# EasyPlanter_V1.net
KiCad netlist of a schematic drawn in EAGLE
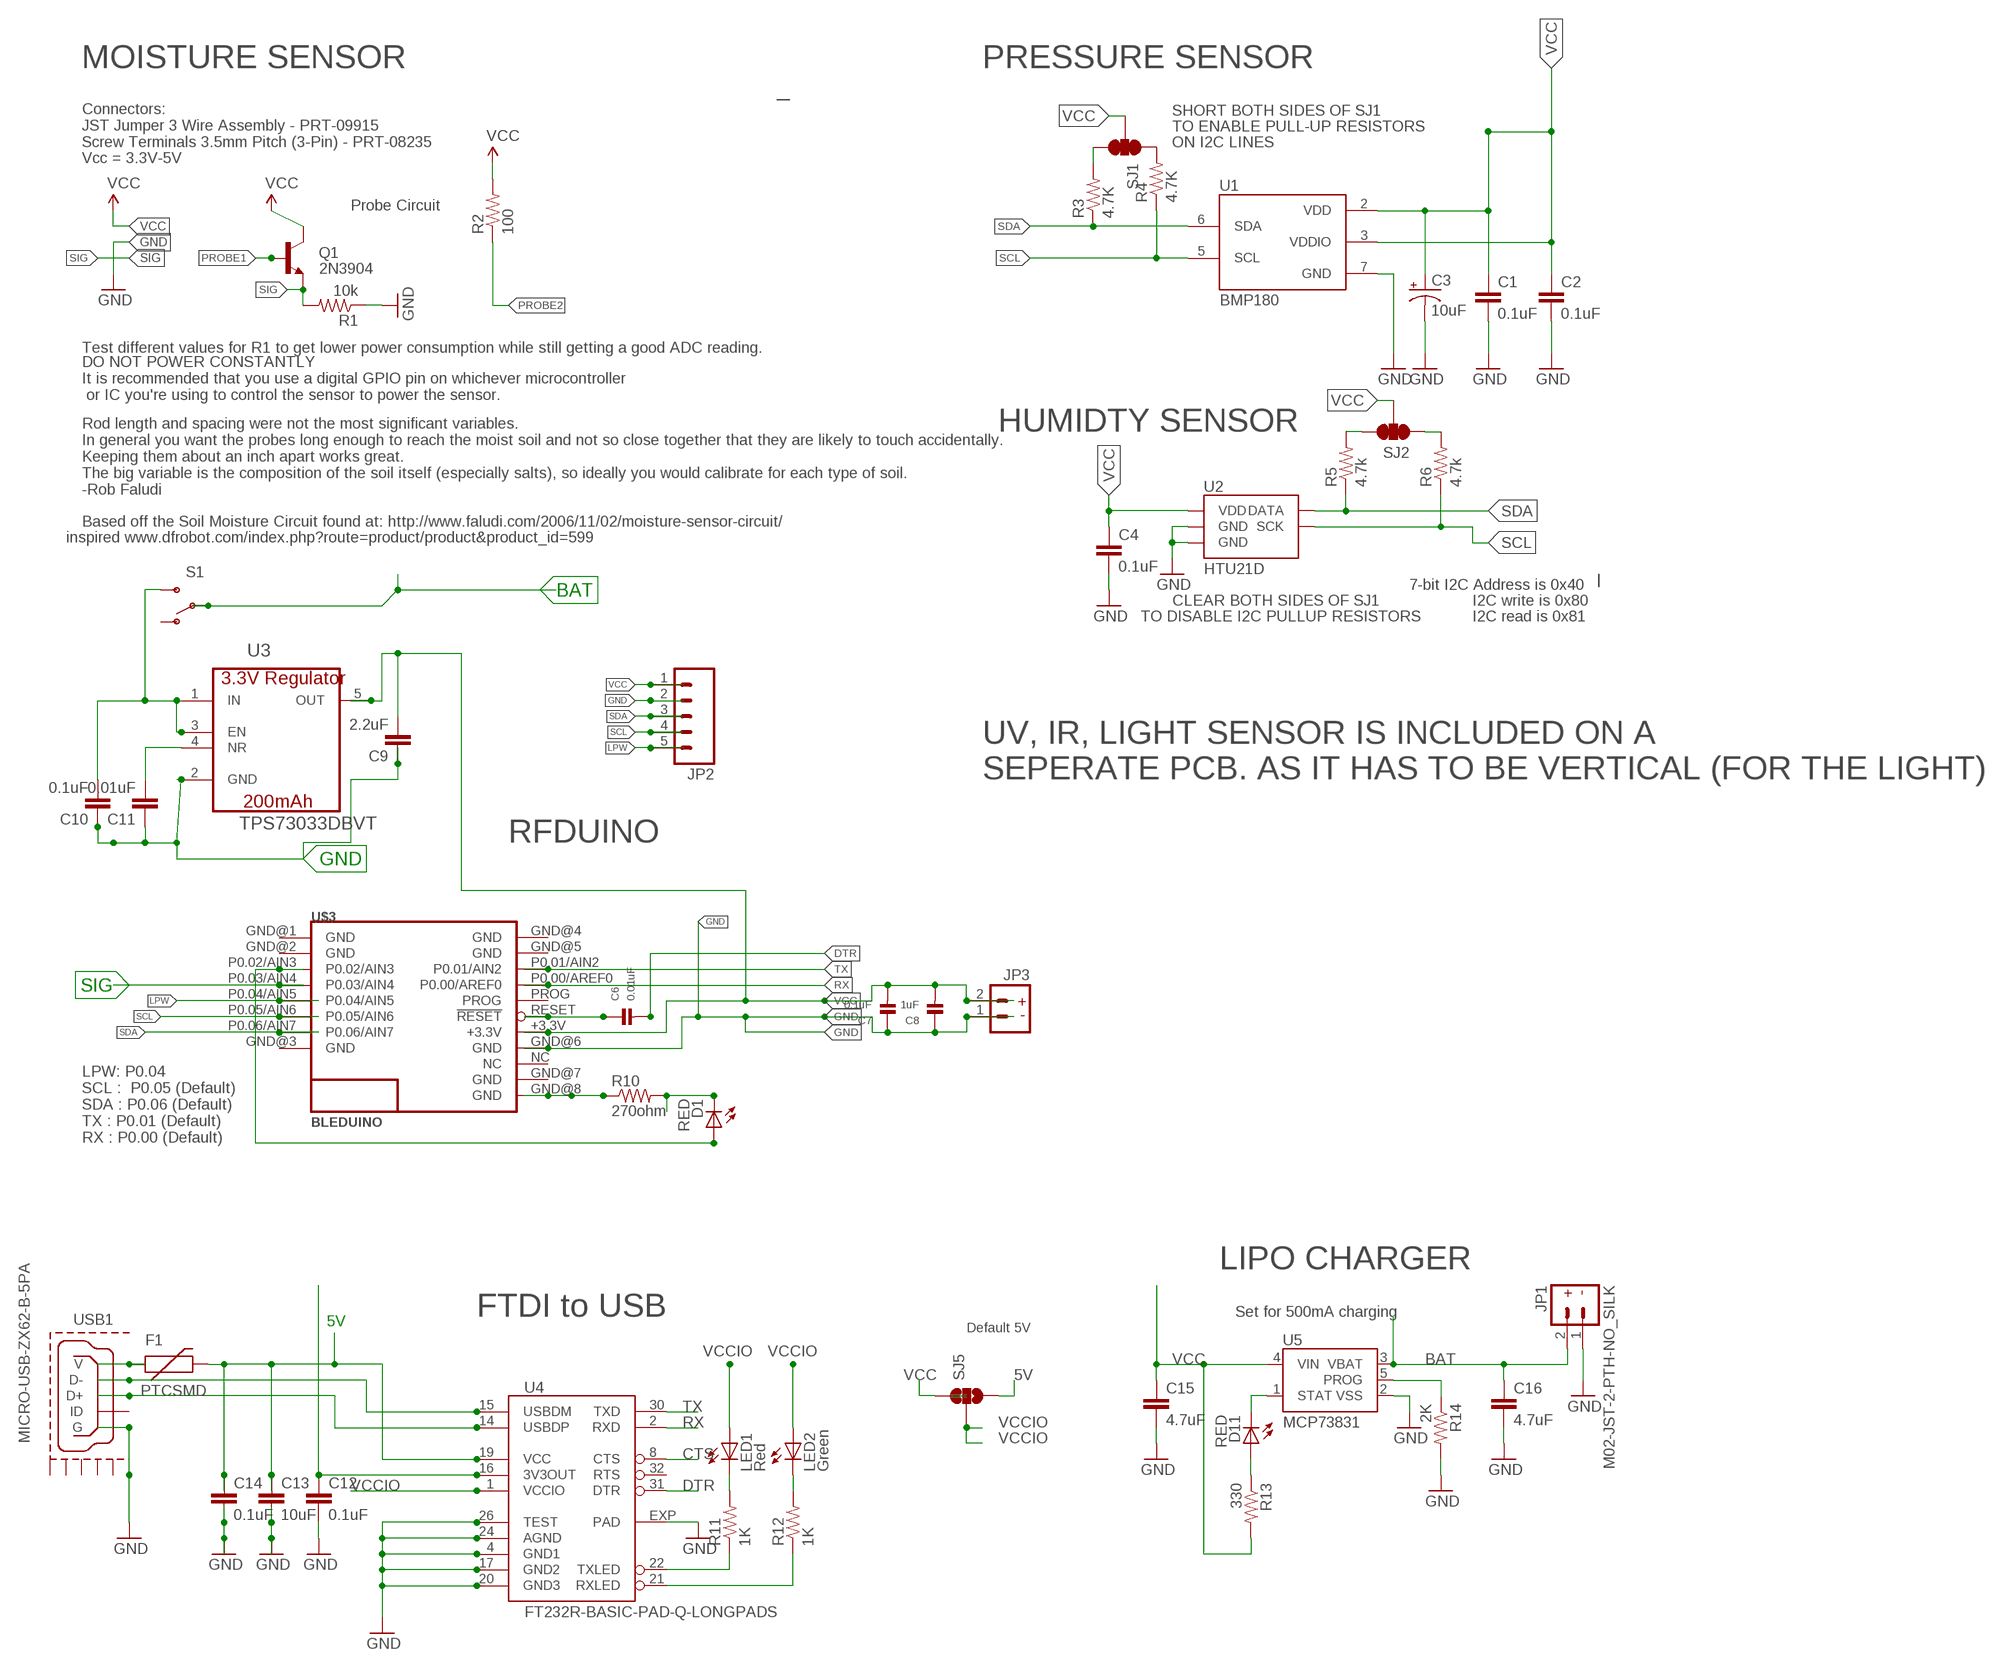
[diagram p0: schematic, sheet 1]

(export (version "E")
  (design (tool "Eeschema 10.0.6"))
  (components
    (comp (ref "C1")
      (value "0.1uF")
      (footprint "eagle-import:0603-CAP")
      (libsource (lib "eagle-import") (part "SparkFun-Capacitors_CAP0603-CAP"))
    )
    (comp (ref "C2")
      (value "0.1uF")
      (footprint "eagle-import:0603-CAP")
      (libsource (lib "eagle-import") (part "SparkFun-Capacitors_CAP0603-CAP"))
    )
    (comp (ref "C3")
      (value "10uF")
      (footprint "eagle-import:EIA3216")
      (libsource (lib "eagle-import") (part "10UF-16V-10%(TANT)"))
    )
    (comp (ref "C4")
      (value "0.1uF")
      (footprint "eagle-import:0603-CAP")
      (libsource (lib "eagle-import") (part "CAP0603-CAP"))
    )
    (comp (ref "C6")
      (value "0.01uF")
      (footprint "eagle-import:0402")
      (libsource (lib "eagle-import") (part "CAP_CERAMIC0402"))
    )
    (comp (ref "C7")
      (value "0.1uF")
      (footprint "eagle-import:0402")
      (libsource (lib "eagle-import") (part "CAP_CERAMIC0402"))
    )
    (comp (ref "C8")
      (value "1uF")
      (footprint "eagle-import:0402")
      (libsource (lib "eagle-import") (part "CAP_CERAMIC0402"))
    )
    (comp (ref "C9")
      (value "2.2uF")
      (footprint "eagle-import:0402-CAP")
      (libsource (lib "eagle-import") (part "CAP0402-CAP"))
    )
    (comp (ref "C10")
      (value "0.1uF")
      (footprint "eagle-import:0402-CAP")
      (libsource (lib "eagle-import") (part "CAP0402-CAP"))
    )
    (comp (ref "C11")
      (value "0.01uF")
      (footprint "eagle-import:0402-CAP")
      (libsource (lib "eagle-import") (part "CAP0402-CAP"))
    )
    (comp (ref "C12")
      (value "0.1uF")
      (footprint "eagle-import:0402-CAP")
      (libsource (lib "eagle-import") (part "CAP-0402"))
    )
    (comp (ref "C13")
      (value "10uF")
      (footprint "eagle-import:0402-CAP")
      (libsource (lib "eagle-import") (part "CAP-0402"))
    )
    (comp (ref "C14")
      (value "0.1uF")
      (footprint "eagle-import:0402-CAP")
      (libsource (lib "eagle-import") (part "CAP-0402"))
    )
    (comp (ref "C15")
      (value "4.7uF")
      (footprint "eagle-import:0402-CAP")
      (libsource (lib "eagle-import") (part "CAP0402-CAP"))
    )
    (comp (ref "C16")
      (value "4.7uF")
      (footprint "eagle-import:0402-CAP")
      (libsource (lib "eagle-import") (part "CAP0402-CAP"))
    )
    (comp (ref "D1")
      (value "RED")
      (footprint "eagle-import:LED-0603")
      (libsource (lib "eagle-import") (part "LED-RED0603"))
    )
    (comp (ref "D11")
      (value "RED")
      (footprint "eagle-import:LED-0603")
      (libsource (lib "eagle-import") (part "LED0603"))
    )
    (comp (ref "F1")
      (value "PTCSMD")
      (footprint "eagle-import:PTC-1206")
      (libsource (lib "eagle-import") (part "PTCSMD"))
    )
    (comp (ref "JP1")
      (value "M02-JST-2-PTH-NO_SILK")
      (footprint "eagle-import:JST-2-PTH-NS")
      (libsource (lib "eagle-import") (part "M02-JST-2-PTH-NO_SILK"))
    )
    (comp (ref "JP2")
      (value "M05PTH")
      (footprint "eagle-import:1X05")
      (libsource (lib "eagle-import") (part "M05PTH"))
    )
    (comp (ref "JP3")
      (value "M02-JST-2-PTH-NO_SILK")
      (footprint "eagle-import:JST-2-PTH-NS")
      (libsource (lib "eagle-import") (part "M02-JST-2-PTH-NO_SILK"))
    )
    (comp (ref "LED1")
      (value "Red")
      (footprint "eagle-import:LED-0603")
      (libsource (lib "eagle-import") (part "akafugu_LED0603"))
    )
    (comp (ref "LED2")
      (value "Green")
      (footprint "eagle-import:LED-0603")
      (libsource (lib "eagle-import") (part "akafugu_LED0603"))
    )
    (comp (ref "Q1")
      (value "2N3904")
      (footprint "eagle-import:SOT23-3")
      (libsource (lib "eagle-import") (part "TRANSISTOR_NPNMMBT2222A"))
    )
    (comp (ref "R1")
      (value "10k")
      (footprint "eagle-import:0603-RES")
      (libsource (lib "eagle-import") (part "100OHM-1/4W-5%(0603)"))
    )
    (comp (ref "R2")
      (value "100")
      (footprint "eagle-import:0603-RES")
      (libsource (lib "eagle-import") (part "100OHM-1/4W-5%(0603)"))
    )
    (comp (ref "R3")
      (value "4.7K")
      (footprint "eagle-import:0603-RES")
      (libsource (lib "eagle-import") (part "SparkFun-Passives_RESISTOR0603-RES"))
    )
    (comp (ref "R4")
      (value "4.7K")
      (footprint "eagle-import:0603-RES")
      (libsource (lib "eagle-import") (part "SparkFun-Passives_RESISTOR0603-RES"))
    )
    (comp (ref "R5")
      (value "4.7k")
      (footprint "eagle-import:0603-RES")
      (libsource (lib "eagle-import") (part "RESISTOR0603-RES"))
    )
    (comp (ref "R6")
      (value "4.7k")
      (footprint "eagle-import:0603-RES")
      (libsource (lib "eagle-import") (part "RESISTOR0603-RES"))
    )
    (comp (ref "R10")
      (value "270ohm")
      (footprint "eagle-import:0402-RES")
      (libsource (lib "eagle-import") (part "SparkFun-Passives_RESISTOR0402-RES"))
    )
    (comp (ref "R11")
      (value "1K")
      (footprint "eagle-import:R0402")
      (libsource (lib "eagle-import") (part "RESISTOR-0402"))
    )
    (comp (ref "R12")
      (value "1K")
      (footprint "eagle-import:R0402")
      (libsource (lib "eagle-import") (part "RESISTOR-0402"))
    )
    (comp (ref "R13")
      (value "330")
      (footprint "eagle-import:0402-RES")
      (libsource (lib "eagle-import") (part "RESISTOR0402-RES"))
    )
    (comp (ref "R14")
      (value "2K")
      (footprint "eagle-import:0402-RES")
      (libsource (lib "eagle-import") (part "RESISTOR0402-RES"))
    )
    (comp (ref "S1")
      (value "SWITCH-SPDT-SMD-A")
      (footprint "eagle-import:SWITCH-SPST-SMD-A")
      (libsource (lib "eagle-import") (part "SWITCH-SPDT-SMD-A"))
    )
    (comp (ref "SJ1")
      (value "SOLDERJUMPER_2WAYPASTE1&2&3")
      (footprint "eagle-import:SJ_3_PASTE1&2&3")
      (libsource (lib "eagle-import") (part "SOLDERJUMPER_2WAYPASTE1&2&3"))
    )
    (comp (ref "SJ2")
      (value "SOLDERJUMPER_2WAYPASTE1&2&3")
      (footprint "eagle-import:SJ_3_PASTE1&2&3")
      (libsource (lib "eagle-import") (part "SOLDERJUMPER_2WAYPASTE1&2&3"))
    )
    (comp (ref "SJ5")
      (value "SOLDERJUMPER_2WAY-LEFT-BRIDGED")
      (footprint "eagle-import:SJ-3-LEFT")
      (libsource (lib "eagle-import") (part "SOLDERJUMPER_2WAY-LEFT-BRIDGED"))
    )
    (comp (ref "U$3")
      (value "BLEDUINO")
      (footprint "eagle-import:BLEDUINO")
      (libsource (lib "eagle-import") (part "BLEDUINO"))
    )
    (comp (ref "U1")
      (value "BMP180")
      (footprint "eagle-import:BMP180")
      (libsource (lib "eagle-import") (part "BMP180"))
    )
    (comp (ref "U2")
      (value "HTU21D")
      (footprint "eagle-import:HTU21D")
      (libsource (lib "eagle-import") (part "HTU21DSMD"))
    )
    (comp (ref "U3")
      (value "TPS73033DBVT")
      (footprint "eagle-import:SOT95P290X145-5N")
      (libsource (lib "eagle-import") (part "TPS73033DBVT"))
    )
    (comp (ref "U4")
      (value "FT232R-BASIC-PAD-Q-LONGPADS")
      (footprint "eagle-import:QFN32-LONG")
      (libsource (lib "eagle-import") (part "FT232R-BASIC-PAD-Q-LONGPADS"))
    )
    (comp (ref "U5")
      (value "MCP73831")
      (footprint "eagle-import:SOT23-5")
      (libsource (lib "eagle-import") (part "MCP73831"))
    )
    (comp (ref "USB1")
      (value "MICRO-USB-ZX62-B-5PA")
      (footprint "eagle-import:ZX62-B-5PA")
      (libsource (lib "eagle-import") (part "MICRO-USB-ZX62-B-5PA"))
    )
  )
  (nets
    (net (code "1") (name "/5V") (class "Default")
      (node (ref "C13") (pin "1") (pinfunction "1_1") (pintype "passive"))
      (node (ref "C14") (pin "1") (pinfunction "1_1") (pintype "passive"))
      (node (ref "F1") (pin "2") (pinfunction "2_2") (pintype "bidirectional"))
      (node (ref "SJ5") (pin "3") (pinfunction "3_3") (pintype "passive"))
      (node (ref "U4") (pin "19") (pinfunction "VCC_19") (pintype "power_in"))
    )
    (net (code "2") (name "/CTS") (class "Default")
      (node (ref "U4") (pin "8") (pinfunction "CTS_8") (pintype "bidirectional"))
    )
    (net (code "3") (name "/GND1") (class "Default")
      (node (ref "USB1") (pin "GND@1") (pinfunction "GND1_GND@1") (pintype "power_in"))
    )
    (net (code "4") (name "/GND2") (class "Default")
      (node (ref "USB1") (pin "GND@2") (pinfunction "GND2_GND@2") (pintype "power_in"))
    )
    (net (code "5") (name "/GND3") (class "Default")
      (node (ref "USB1") (pin "GND@3") (pinfunction "GND3_GND@3") (pintype "power_in"))
    )
    (net (code "6") (name "/GND4") (class "Default")
      (node (ref "USB1") (pin "GND@4") (pinfunction "GND4_GND@4") (pintype "power_in"))
    )
    (net (code "7") (name "/GND5") (class "Default")
      (node (ref "USB1") (pin "GND@5") (pinfunction "GND5_GND@5") (pintype "power_in"))
    )
    (net (code "8") (name "/VCCIO") (class "Default")
      (node (ref "LED1") (pin "A") (pinfunction "A_A") (pintype "passive"))
      (node (ref "LED2") (pin "A") (pinfunction "A_A") (pintype "passive"))
      (node (ref "SJ5") (pin "2") (pinfunction "2_2") (pintype "passive"))
      (node (ref "U4") (pin "1") (pinfunction "VCCIO_1") (pintype "power_in"))
    )
    (net (code "9") (name "BAT") (class "Default")
      (node (ref "C16") (pin "1") (pinfunction "1_1") (pintype "passive"))
      (node (ref "JP1") (pin "2") (pinfunction "2_2") (pintype "passive"))
      (node (ref "S1") (pin "2") (pinfunction "P_2") (pintype "passive"))
      (node (ref "U5") (pin "3") (pinfunction "VBAT_3") (pintype "power_in"))
    )
    (net (code "10") (name "DTR") (class "Default")
      (node (ref "C6") (pin "2") (pinfunction "P$2_2") (pintype "passive"))
      (node (ref "U4") (pin "31") (pinfunction "DTR_31") (pintype "bidirectional"))
    )
    (net (code "11") (name "GND") (class "Default")
      (node (ref "C1") (pin "2") (pinfunction "2_2") (pintype "passive"))
      (node (ref "C10") (pin "1") (pinfunction "1_1") (pintype "passive"))
      (node (ref "C11") (pin "1") (pinfunction "1_1") (pintype "passive"))
      (node (ref "C12") (pin "2") (pinfunction "2_2") (pintype "passive"))
      (node (ref "C13") (pin "2") (pinfunction "2_2") (pintype "passive"))
      (node (ref "C14") (pin "2") (pinfunction "2_2") (pintype "passive"))
      (node (ref "C15") (pin "2") (pinfunction "2_2") (pintype "passive"))
      (node (ref "C16") (pin "2") (pinfunction "2_2") (pintype "passive"))
      (node (ref "C2") (pin "2") (pinfunction "2_2") (pintype "passive"))
      (node (ref "C3") (pin "C") (pinfunction "-_C") (pintype "passive"))
      (node (ref "C4") (pin "2") (pinfunction "2_2") (pintype "passive"))
      (node (ref "C7") (pin "1") (pinfunction "P$1_1") (pintype "passive"))
      (node (ref "C8") (pin "1") (pinfunction "P$1_1") (pintype "passive"))
      (node (ref "C9") (pin "1") (pinfunction "1_1") (pintype "passive"))
      (node (ref "JP1") (pin "1") (pinfunction "1_1") (pintype "passive"))
      (node (ref "JP2") (pin "2") (pinfunction "2_2") (pintype "passive"))
      (node (ref "JP3") (pin "1") (pinfunction "1_1") (pintype "passive"))
      (node (ref "R1") (pin "1") (pinfunction "1_1") (pintype "passive"))
      (node (ref "R14") (pin "2") (pinfunction "2_2") (pintype "passive"))
      (node (ref "U$3") (pin "GND@6") (pinfunction "GND_GND@6") (pintype "bidirectional"))
      (node (ref "U1") (pin "7") (pinfunction "GND_7") (pintype "power_in"))
      (node (ref "U2") (pin "7") (pinfunction "GND_7") (pintype "power_in"))
      (node (ref "U2") (pin "GND") (pinfunction "GND_GND") (pintype "power_in"))
      (node (ref "U3") (pin "2") (pinfunction "GND_2") (pintype "passive"))
      (node (ref "U4") (pin "17") (pinfunction "GND2_17") (pintype "power_in"))
      (node (ref "U4") (pin "20") (pinfunction "GND3_20") (pintype "power_in"))
      (node (ref "U4") (pin "24") (pinfunction "AGND_24") (pintype "power_in"))
      (node (ref "U4") (pin "26") (pinfunction "TEST_26") (pintype "input"))
      (node (ref "U4") (pin "4") (pinfunction "GND1_4") (pintype "power_in"))
      (node (ref "U4") (pin "EXP") (pinfunction "PAD_EXP") (pintype "bidirectional"))
      (node (ref "U5") (pin "2") (pinfunction "VSS_2") (pintype "power_in"))
      (node (ref "USB1") (pin "5") (pinfunction "G_5") (pintype "input"))
      (node (ref "USB1") (pin "GND@6") (pinfunction "GND6_GND@6") (pintype "power_in"))
    )
    (net (code "12") (name "LPW") (class "Default")
      (node (ref "JP2") (pin "5") (pinfunction "5_5") (pintype "passive"))
      (node (ref "U$3") (pin "P0.04/AIN5") (pinfunction "P0.04/AIN5_P0.04/AIN5") (pintype "bidirectional"))
    )
    (net (code "13") (name "Net-(C6-P$1)") (class "Default")
      (node (ref "C6") (pin "1") (pinfunction "P$1_1") (pintype "passive"))
      (node (ref "U$3") (pin "RESET") (pinfunction "~{RESET}_RESET") (pintype "bidirectional"))
    )
    (net (code "14") (name "Net-(D1-PadA)") (class "Default")
      (node (ref "D1") (pin "A") (pinfunction "A_A") (pintype "passive"))
      (node (ref "U$3") (pin "P0.02/AIN3") (pinfunction "P0.02/AIN3_P0.02/AIN3") (pintype "bidirectional"))
    )
    (net (code "15") (name "Net-(D1-PadC)") (class "Default")
      (node (ref "D1") (pin "C") (pinfunction "C_C") (pintype "passive"))
      (node (ref "R10") (pin "2") (pinfunction "2_2") (pintype "passive"))
    )
    (net (code "16") (name "Net-(D11-PadA)") (class "Default")
      (node (ref "D11") (pin "A") (pinfunction "A_A") (pintype "passive"))
      (node (ref "R13") (pin "1") (pinfunction "1_1") (pintype "passive"))
    )
    (net (code "17") (name "Net-(LED1-PadC)") (class "Default")
      (node (ref "LED1") (pin "C") (pinfunction "C_C") (pintype "passive"))
      (node (ref "R11") (pin "2") (pinfunction "2_2") (pintype "passive"))
    )
    (net (code "18") (name "Net-(LED2-PadC)") (class "Default")
      (node (ref "LED2") (pin "C") (pinfunction "C_C") (pintype "passive"))
      (node (ref "R12") (pin "2") (pinfunction "2_2") (pintype "passive"))
    )
    (net (code "19") (name "Net-(R3-Pad2)") (class "Default")
      (node (ref "R3") (pin "2") (pinfunction "2_2") (pintype "passive"))
      (node (ref "SJ1") (pin "3") (pinfunction "3_3") (pintype "passive"))
    )
    (net (code "20") (name "Net-(R4-Pad2)") (class "Default")
      (node (ref "R4") (pin "2") (pinfunction "2_2") (pintype "passive"))
      (node (ref "SJ1") (pin "1") (pinfunction "1_1") (pintype "passive"))
    )
    (net (code "21") (name "Net-(R5-Pad2)") (class "Default")
      (node (ref "R5") (pin "2") (pinfunction "2_2") (pintype "passive"))
      (node (ref "SJ2") (pin "3") (pinfunction "3_3") (pintype "passive"))
    )
    (net (code "22") (name "Net-(R6-Pad2)") (class "Default")
      (node (ref "R6") (pin "2") (pinfunction "2_2") (pintype "passive"))
      (node (ref "SJ2") (pin "1") (pinfunction "1_1") (pintype "passive"))
    )
    (net (code "23") (name "Net-(R10-Pad1)") (class "Default")
      (node (ref "R10") (pin "1") (pinfunction "1_1") (pintype "passive"))
      (node (ref "U$3") (pin "GND@8") (pinfunction "GND_GND@8") (pintype "bidirectional"))
    )
    (net (code "24") (name "Net-(S1-S)") (class "Default")
      (node (ref "C10") (pin "2") (pinfunction "2_2") (pintype "passive"))
      (node (ref "S1") (pin "3") (pinfunction "S_3") (pintype "passive"))
      (node (ref "U3") (pin "1") (pinfunction "IN_1") (pintype "input"))
      (node (ref "U3") (pin "3") (pinfunction "EN_3") (pintype "input"))
    )
    (net (code "25") (name "Net-(U3-NR)") (class "Default")
      (node (ref "C11") (pin "2") (pinfunction "2_2") (pintype "passive"))
      (node (ref "U3") (pin "4") (pinfunction "NR_4") (pintype "input"))
    )
    (net (code "26") (name "Net-(U4-RXLED)") (class "Default")
      (node (ref "R12") (pin "1") (pinfunction "1_1") (pintype "passive"))
      (node (ref "U4") (pin "21") (pinfunction "RXLED_21") (pintype "bidirectional"))
    )
    (net (code "27") (name "Net-(U4-TXLED)") (class "Default")
      (node (ref "R11") (pin "1") (pinfunction "1_1") (pintype "passive"))
      (node (ref "U4") (pin "22") (pinfunction "TXLED_22") (pintype "bidirectional"))
    )
    (net (code "28") (name "Net-(U4-USBDM)") (class "Default")
      (node (ref "U4") (pin "15") (pinfunction "USBDM_15") (pintype "bidirectional"))
      (node (ref "USB1") (pin "2") (pinfunction "D-_2") (pintype "input"))
    )
    (net (code "29") (name "Net-(U4-USBDP)") (class "Default")
      (node (ref "U4") (pin "14") (pinfunction "USBDP_14") (pintype "bidirectional"))
      (node (ref "USB1") (pin "3") (pinfunction "D+_3") (pintype "input"))
    )
    (net (code "30") (name "Net-(U5-PROG)") (class "Default")
      (node (ref "R14") (pin "1") (pinfunction "1_1") (pintype "passive"))
      (node (ref "U5") (pin "5") (pinfunction "PROG_5") (pintype "input"))
    )
    (net (code "31") (name "Net-(U5-STAT)") (class "Default")
      (node (ref "D11") (pin "C") (pinfunction "C_C") (pintype "passive"))
      (node (ref "U5") (pin "1") (pinfunction "STAT_1") (pintype "output"))
    )
    (net (code "32") (name "Net-(USB1-V)") (class "Default")
      (node (ref "F1") (pin "1") (pinfunction "1_1") (pintype "bidirectional"))
      (node (ref "USB1") (pin "1") (pinfunction "V_1") (pintype "input"))
    )
    (net (code "33") (name "PROBE1") (class "Default")
      (node (ref "Q1") (pin "1") (pinfunction "B_1") (pintype "passive"))
    )
    (net (code "34") (name "PROBE2") (class "Default")
      (node (ref "R2") (pin "1") (pinfunction "1_1") (pintype "passive"))
    )
    (net (code "35") (name "RX") (class "Default")
      (node (ref "U$3") (pin "P0.00/AREF0") (pinfunction "P0.00/AREF0_P0.00/AREF0") (pintype "bidirectional"))
      (node (ref "U4") (pin "2") (pinfunction "RXD_2") (pintype "input"))
    )
    (net (code "36") (name "SCL") (class "Default")
      (node (ref "JP2") (pin "4") (pinfunction "4_4") (pintype "passive"))
      (node (ref "R4") (pin "1") (pinfunction "1_1") (pintype "passive"))
      (node (ref "R6") (pin "1") (pinfunction "1_1") (pintype "passive"))
      (node (ref "U$3") (pin "P0.05/AIN6") (pinfunction "P0.05/AIN6_P0.05/AIN6") (pintype "bidirectional"))
      (node (ref "U1") (pin "5") (pinfunction "SCL_5") (pintype "input"))
      (node (ref "U2") (pin "SCK") (pinfunction "SCK_SCK") (pintype "input"))
    )
    (net (code "37") (name "SDA") (class "Default")
      (node (ref "JP2") (pin "3") (pinfunction "3_3") (pintype "passive"))
      (node (ref "R3") (pin "1") (pinfunction "1_1") (pintype "passive"))
      (node (ref "R5") (pin "1") (pinfunction "1_1") (pintype "passive"))
      (node (ref "U$3") (pin "P0.06/AIN7") (pinfunction "P0.06/AIN7_P0.06/AIN7") (pintype "bidirectional"))
      (node (ref "U1") (pin "6") (pinfunction "SDA_6") (pintype "bidirectional"))
      (node (ref "U2") (pin "DATA") (pinfunction "DATA_DATA") (pintype "bidirectional"))
    )
    (net (code "38") (name "SIG") (class "Default")
      (node (ref "Q1") (pin "2") (pinfunction "E_2") (pintype "passive"))
      (node (ref "R1") (pin "2") (pinfunction "2_2") (pintype "passive"))
      (node (ref "U$3") (pin "P0.03/AIN4") (pinfunction "P0.03/AIN4_P0.03/AIN4") (pintype "bidirectional"))
    )
    (net (code "39") (name "TX") (class "Default")
      (node (ref "U$3") (pin "P0.01/AIN2") (pinfunction "P0.01/AIN2_P0.01/AIN2") (pintype "bidirectional"))
      (node (ref "U4") (pin "30") (pinfunction "TXD_30") (pintype "output"))
    )
    (net (code "40") (name "VCC") (class "Default")
      (node (ref "C1") (pin "1") (pinfunction "1_1") (pintype "passive"))
      (node (ref "C12") (pin "1") (pinfunction "1_1") (pintype "passive"))
      (node (ref "C15") (pin "1") (pinfunction "1_1") (pintype "passive"))
      (node (ref "C2") (pin "1") (pinfunction "1_1") (pintype "passive"))
      (node (ref "C3") (pin "A") (pinfunction "+_A") (pintype "passive"))
      (node (ref "C4") (pin "1") (pinfunction "1_1") (pintype "passive"))
      (node (ref "C7") (pin "2") (pinfunction "P$2_2") (pintype "passive"))
      (node (ref "C8") (pin "2") (pinfunction "P$2_2") (pintype "passive"))
      (node (ref "C9") (pin "2") (pinfunction "2_2") (pintype "passive"))
      (node (ref "JP2") (pin "1") (pinfunction "1_1") (pintype "passive"))
      (node (ref "JP3") (pin "2") (pinfunction "2_2") (pintype "passive"))
      (node (ref "Q1") (pin "3") (pinfunction "C_3") (pintype "passive"))
      (node (ref "R13") (pin "2") (pinfunction "2_2") (pintype "passive"))
      (node (ref "R2") (pin "2") (pinfunction "2_2") (pintype "passive"))
      (node (ref "SJ1") (pin "2") (pinfunction "2_2") (pintype "passive"))
      (node (ref "SJ2") (pin "2") (pinfunction "2_2") (pintype "passive"))
      (node (ref "SJ5") (pin "1") (pinfunction "1_1") (pintype "passive"))
      (node (ref "U$3") (pin "+3.3V") (pinfunction "+3.3V_+3.3V") (pintype "bidirectional"))
      (node (ref "U1") (pin "2") (pinfunction "VDD_2") (pintype "power_in"))
      (node (ref "U1") (pin "3") (pinfunction "VDDIO_3") (pintype "power_in"))
      (node (ref "U2") (pin "VDD") (pinfunction "VDD_VDD") (pintype "power_in"))
      (node (ref "U3") (pin "5") (pinfunction "OUT_5") (pintype "output"))
      (node (ref "U4") (pin "16") (pinfunction "3V3OUT_16") (pintype "output"))
      (node (ref "U5") (pin "4") (pinfunction "VIN_4") (pintype "power_in"))
    )
    (net (code "41") (name "unconnected-(S1-O-Pad1)") (class "Default")
      (node (ref "S1") (pin "1") (pinfunction "O_1") (pintype "passive"))
    )
    (net (code "42") (name "unconnected-(U$3-GND-PadGND@1)") (class "Default")
      (node (ref "U$3") (pin "GND@1") (pinfunction "GND_GND@1") (pintype "bidirectional"))
    )
    (net (code "43") (name "unconnected-(U$3-GND-PadGND@2)") (class "Default")
      (node (ref "U$3") (pin "GND@2") (pinfunction "GND_GND@2") (pintype "bidirectional"))
    )
    (net (code "44") (name "unconnected-(U$3-GND-PadGND@3)") (class "Default")
      (node (ref "U$3") (pin "GND@3") (pinfunction "GND_GND@3") (pintype "bidirectional"))
    )
    (net (code "45") (name "unconnected-(U$3-GND-PadGND@4)") (class "Default")
      (node (ref "U$3") (pin "GND@4") (pinfunction "GND_GND@4") (pintype "bidirectional"))
    )
    (net (code "46") (name "unconnected-(U$3-GND-PadGND@5)") (class "Default")
      (node (ref "U$3") (pin "GND@5") (pinfunction "GND_GND@5") (pintype "bidirectional"))
    )
    (net (code "47") (name "unconnected-(U$3-GND-PadGND@7)") (class "Default")
      (node (ref "U$3") (pin "GND@7") (pinfunction "GND_GND@7") (pintype "bidirectional"))
    )
    (net (code "48") (name "unconnected-(U$3-PadNC)") (class "Default")
      (node (ref "U$3") (pin "NC") (pinfunction "NC_NC") (pintype "no_connect"))
    )
    (net (code "49") (name "unconnected-(U$3-PadPROG)") (class "Default")
      (node (ref "U$3") (pin "PROG") (pinfunction "PROG_PROG") (pintype "bidirectional"))
    )
    (net (code "50") (name "unconnected-(U4-RTS-Pad32)") (class "Default")
      (node (ref "U4") (pin "32") (pinfunction "RTS_32") (pintype "bidirectional"))
    )
    (net (code "51") (name "unconnected-(USB1-ID-Pad4)") (class "Default")
      (node (ref "USB1") (pin "4") (pinfunction "ID_4") (pintype "input"))
    )
  )
)
